# Carrier_Board.net
KiCad netlist of a schematic drawn in EAGLE
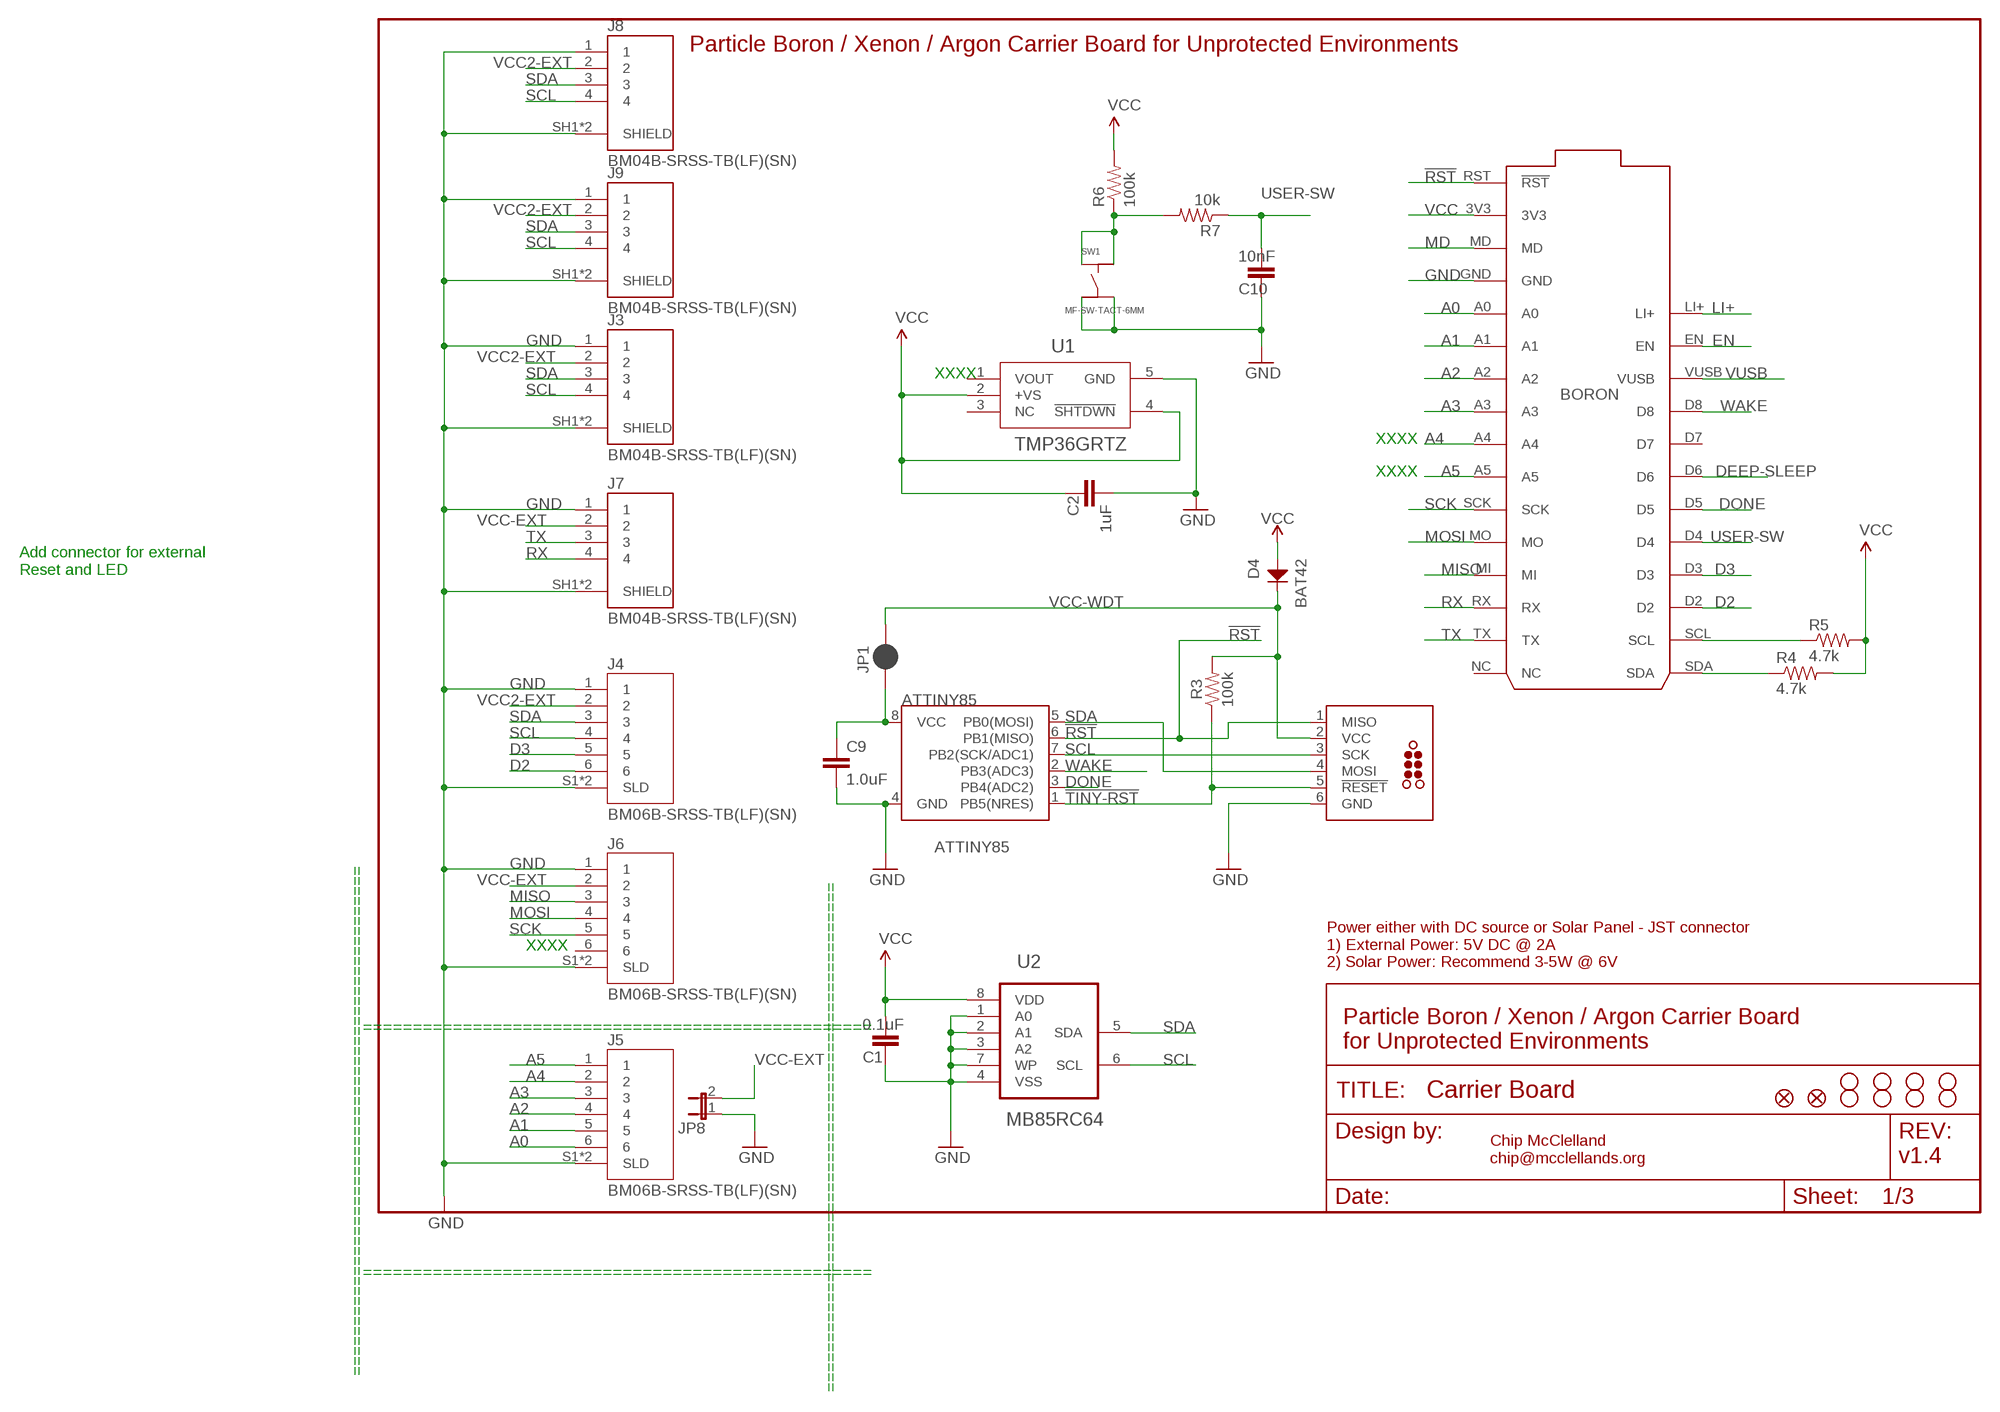
[diagram p0: schematic, sheet 1]
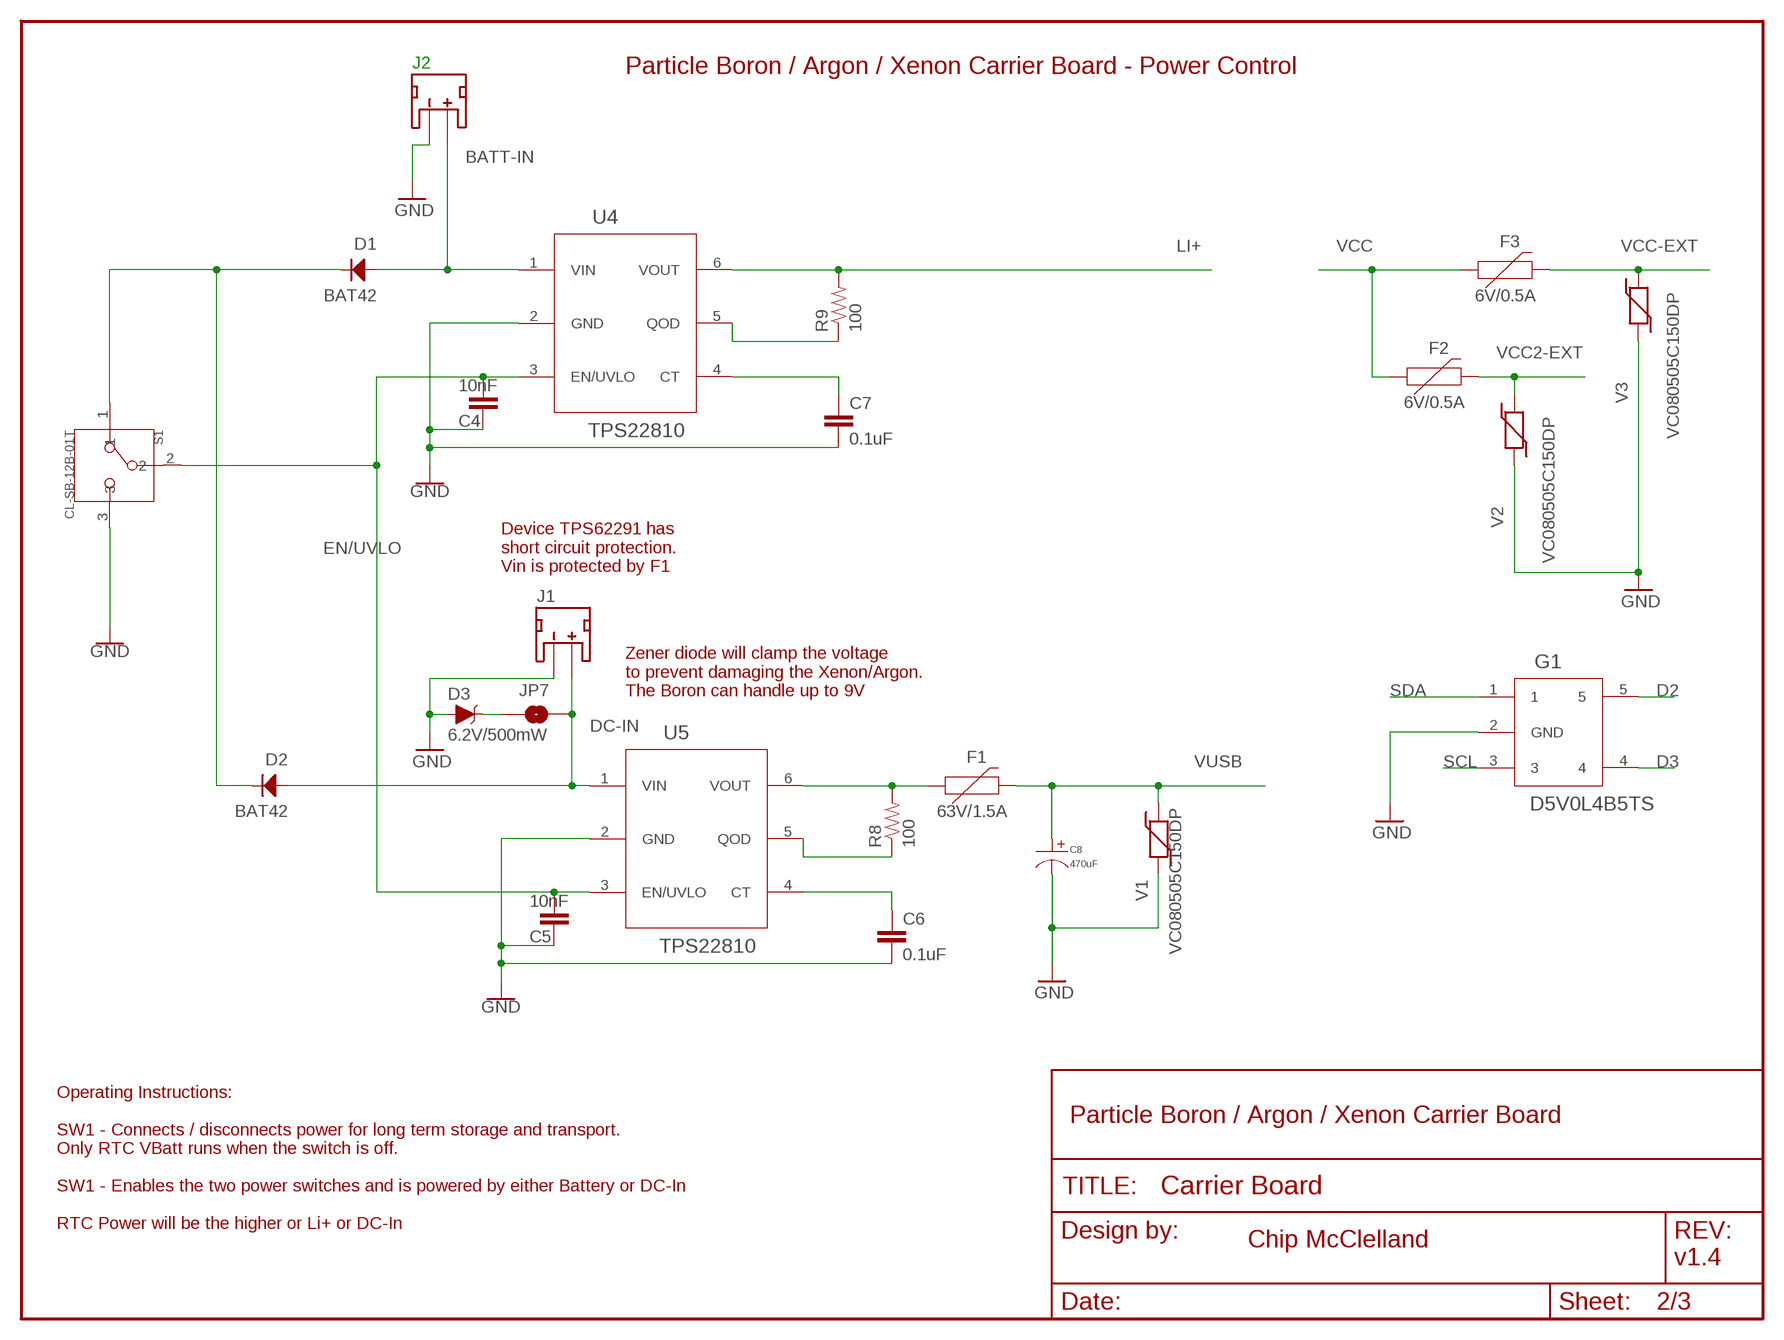
[diagram p1: schematic, sheet 2]
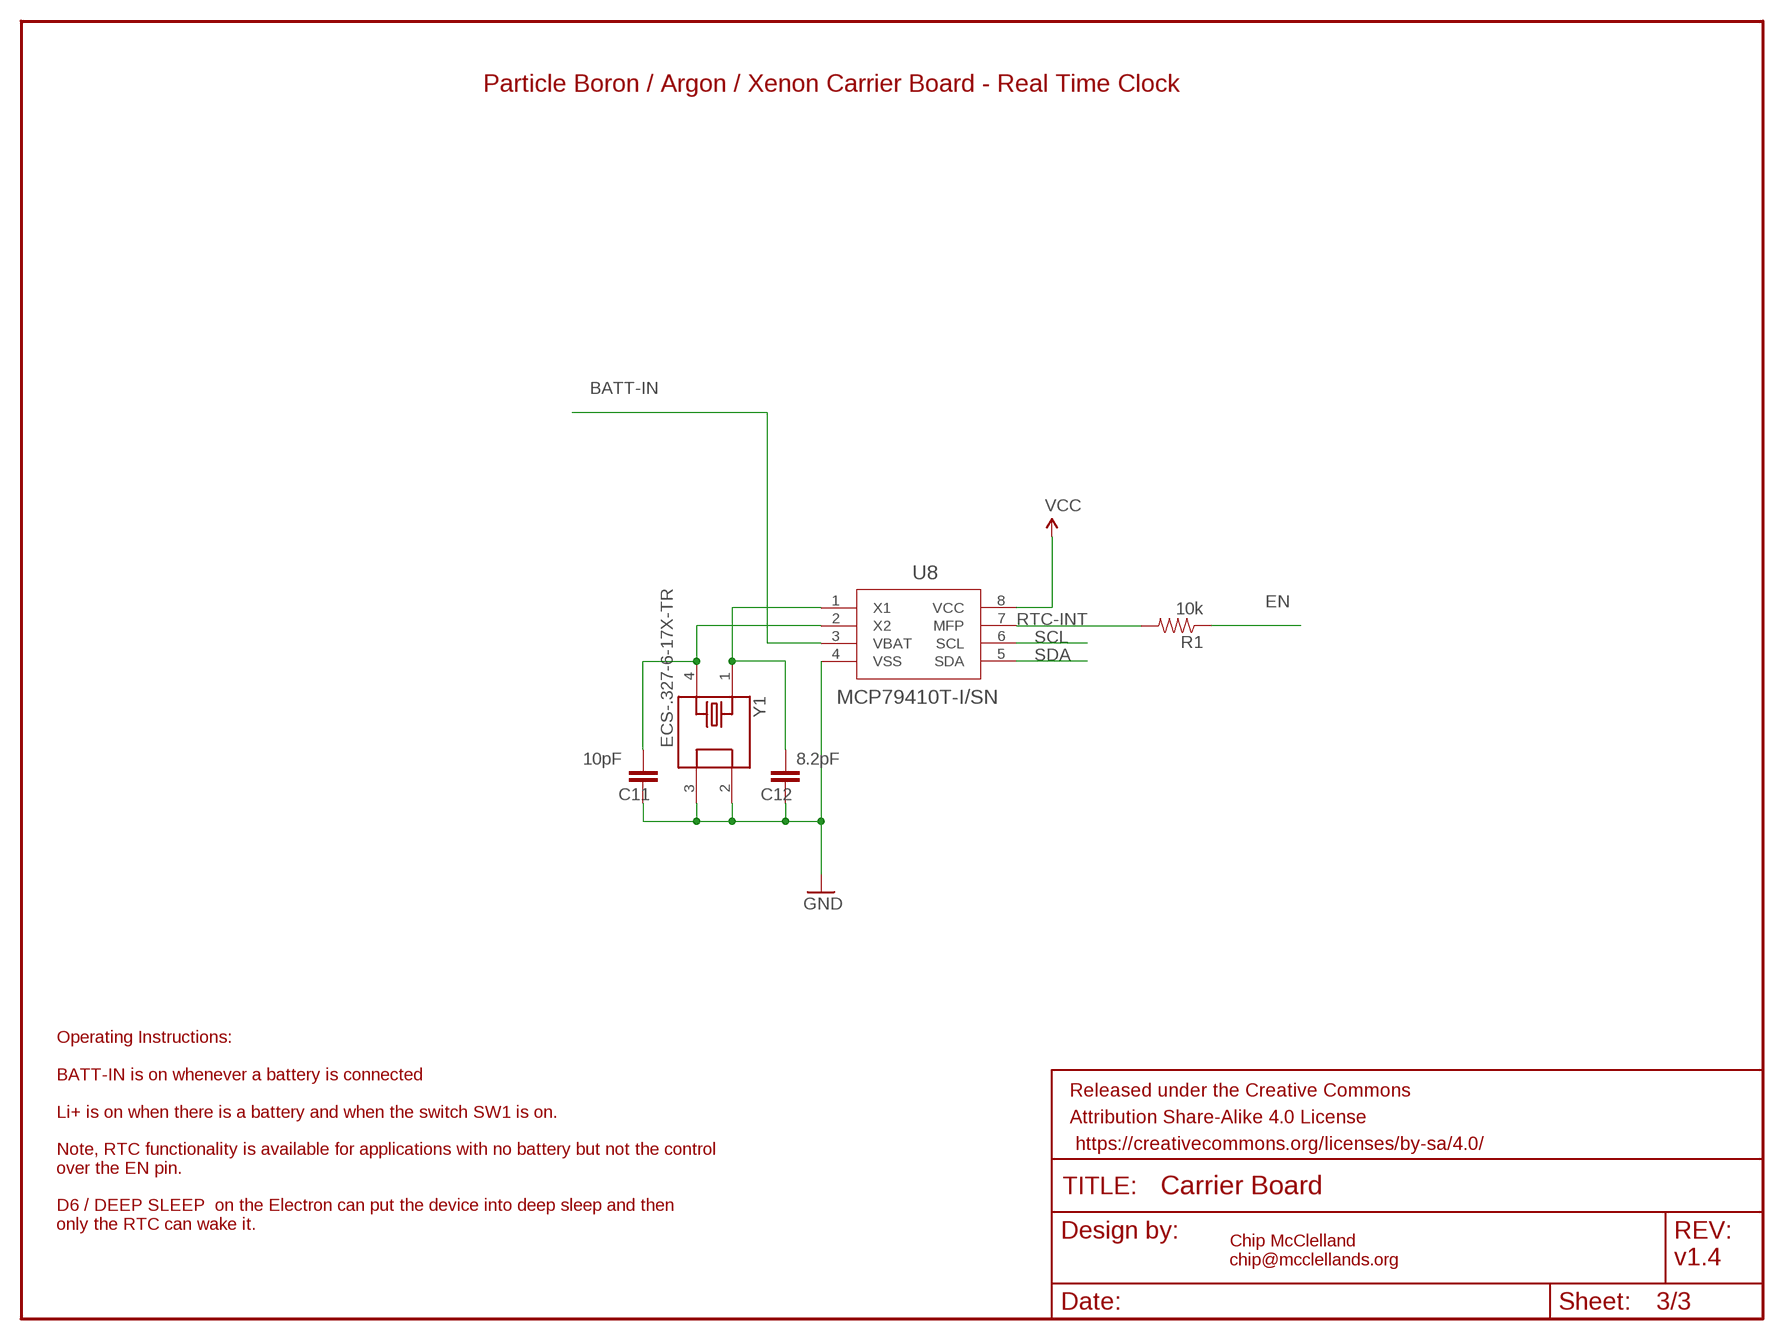
[diagram p2: schematic, sheet 3]

(export (version "E")
  (design (tool "Eeschema 10.0.6"))
  (components
    (comp (ref "C4")
      (value "10nF")
      (footprint "eagle-import:0805@1")
      (fields (field (name "HOUSEPART") "No") (field (name "MPN") "08051C103K4T2A"))
      (libsource (lib "eagle-import") (part "CAP0805"))
    )
    (comp (ref "C5")
      (value "10nF")
      (footprint "eagle-import:0805@1")
      (fields (field (name "HOUSEPART") "No") (field (name "MPN") "08051C103K4T2A"))
      (libsource (lib "eagle-import") (part "CAP0805"))
    )
    (comp (ref "C6")
      (value "0.1uF")
      (footprint "eagle-import:0805@1")
      (fields (field (name "HOUSEPART") "Yes") (field (name "MPN") "MF-CAP-0805-0.1uF"))
      (libsource (lib "eagle-import") (part "CAP0805"))
    )
    (comp (ref "C7")
      (value "0.1uF")
      (footprint "eagle-import:0805@1")
      (fields (field (name "HOUSEPART") "Yes") (field (name "MPN") "MF-CAP-0805-0.1uF"))
      (libsource (lib "eagle-import") (part "CAP0805"))
    )
    (comp (ref "C8")
      (value "470uF")
      (footprint "eagle-import:CP10MM")
      (fields (field (name "HOUSEPART") "1") (field (name "MPN") "MF-CAP-10MM-470uF"))
      (libsource (lib "eagle-import") (part "CAPACITOR_P_10MM"))
    )
    (comp (ref "D1")
      (value "BAT42")
      (footprint "eagle-import:SOD-123")
      (fields (field (name "HOUSEPART") "YES") (field (name "MPN") "MF-DIO-SOD123-BAT42"))
      (libsource (lib "eagle-import") (part "DIODES_SOD-123_BAT42"))
    )
    (comp (ref "D2")
      (value "BAT42")
      (footprint "eagle-import:SOD-123")
      (fields (field (name "HOUSEPART") "YES") (field (name "MPN") "MF-DIO-SOD123-BAT42"))
      (libsource (lib "eagle-import") (part "DIODES_SOD-123_BAT42"))
    )
    (comp (ref "D3")
      (value "6.2V/500mW")
      (footprint "eagle-import:PANASONIC_SMINI2-F5-B")
      (fields (field (name "MPN") "TDZ6V2J,115"))
      (libsource (lib "eagle-import") (part "DIODE-ZENER-DZ2J150M0L"))
    )
    (comp (ref "F1")
      (value "63V/1.5A")
      (footprint "eagle-import:1206")
      (fields (field (name "MPN") "046801.5NR"))
      (libsource (lib "eagle-import") (part "PPTC_HALF-AMP"))
    )
    (comp (ref "F2")
      (value "6V/0.5A")
      (footprint "eagle-import:1206")
      (fields (field (name "MPN") "0466.500NR"))
      (libsource (lib "eagle-import") (part "PPTC_HALF-AMP"))
    )
    (comp (ref "F3")
      (value "6V/0.5A")
      (footprint "eagle-import:1206")
      (fields (field (name "MPN") "0466.500NR"))
      (libsource (lib "eagle-import") (part "PPTC_HALF-AMP"))
    )
    (comp (ref "FRAME2")
      (value "FRAME-LETTER")
      (footprint "eagle-import:CREATIVE_COMMONS")
      (fields (field (name "POPULATE") "0"))
      (libsource (lib "eagle-import") (part "FRAME-LETTER"))
    )
    (comp (ref "G1")
      (value "D5V0L4B5TS")
      (footprint "eagle-import:SOT-23-5")
      (fields (field (name "MPN") "D5V0L4B5TS-7"))
      (libsource (lib "eagle-import") (part "D5V0L4B5TS"))
    )
    (comp (ref "J1")
      (value "S2B-PH-SM4-TB(LF)(SN)")
      (footprint "eagle-import:JST-2-SMD")
      (fields (field (name "MFG") "JST S2B-PH-SM4-TB(LF)(SN)"))
      (libsource (lib "eagle-import") (part "JST_2MM_MALE"))
    )
    (comp (ref "J2")
      (value "S2B-PH-SM4-TB(LF)(SN)")
      (footprint "eagle-import:JST-2-SMD")
      (fields (field (name "MFG") "JST S2B-PH-SM4-TB(LF)(SN)"))
      (libsource (lib "eagle-import") (part "JST_2MM_MALE"))
    )
    (comp (ref "JP7")
      (value "JUMPER-SMT_2_NO_SILK")
      (footprint "eagle-import:SMT-JUMPER_2_NO_SILK")
      (libsource (lib "eagle-import") (part "JUMPER-SMT_2_NO_SILK"))
    )
    (comp (ref "R8")
      (value "100")
      (footprint "eagle-import:0805")
      (fields (field (name "HOUSEPART") "Yes") (field (name "MPN") "MF-RES-0805-100"))
      (libsource (lib "eagle-import") (part "RESISTOR0805-RES"))
    )
    (comp (ref "R9")
      (value "100")
      (footprint "eagle-import:0805")
      (fields (field (name "HOUSEPART") "Yes") (field (name "MPN") "MF-RES-0805-100"))
      (libsource (lib "eagle-import") (part "RESISTOR0805-RES"))
    )
    (comp (ref "S1")
      (value "CL-SB-12B-01T")
      (footprint "eagle-import:CL-SB-12B")
      (fields (field (name "DIGI-KEY_PART_NUMBER") "563-1318-1-ND") (field (name "MF") "Nidec Copal"))
      (libsource (lib "eagle-import") (part "CL-SB-12B-01T"))
    )
    (comp (ref "U4")
      (value "TPS22810")
      (footprint "eagle-import:SOT-23-6")
      (fields (field (name "MPN") "TPS22810DBVT"))
      (libsource (lib "eagle-import") (part "TPS22810"))
    )
    (comp (ref "U5")
      (value "TPS22810")
      (footprint "eagle-import:SOT-23-6")
      (fields (field (name "MPN") "TPS22810DBVT"))
      (libsource (lib "eagle-import") (part "TPS22810"))
    )
    (comp (ref "V1")
      (value "VC080505C150DP")
      (footprint "eagle-import:0805")
      (libsource (lib "eagle-import") (part "VARISTOR"))
    )
    (comp (ref "V2")
      (value "VC080505C150DP")
      (footprint "eagle-import:0805")
      (libsource (lib "eagle-import") (part "VARISTOR"))
    )
    (comp (ref "V3")
      (value "VC080505C150DP")
      (footprint "eagle-import:0805")
      (libsource (lib "eagle-import") (part "VARISTOR"))
    )
    (comp (ref "ATTINY85")
      (value "ATTINY85")
      (footprint "eagle-import:SO08-EIAJ")
      (fields (field (name "MPN") "ATTINY85-20SUR"))
      (libsource (lib "eagle-import") (part "ATTINY45"))
    )
    (comp (ref "C1")
      (value "0.1uF")
      (footprint "eagle-import:0805@1")
      (fields (field (name "HOUSEPART") "YES") (field (name "MPN") "MF-CAP-0805-0.1uF"))
      (libsource (lib "eagle-import") (part "CAP0805"))
    )
    (comp (ref "C2")
      (value "1uF")
      (footprint "eagle-import:0805@1")
      (fields (field (name "MPN") "MF-CAP-0805-1uF"))
      (libsource (lib "eagle-import") (part "CAP0805"))
    )
    (comp (ref "C9")
      (value "1.0uF")
      (footprint "eagle-import:0805")
      (fields (field (name "MPN") "MF-CAP-0805-0.1uF"))
      (libsource (lib "eagle-import") (part "1.0UF-0805-25V-10%"))
    )
    (comp (ref "C10")
      (value "10nF")
      (footprint "eagle-import:0805@1")
      (fields (field (name "HOUSEPART") "No") (field (name "MPN") "08051C103K4T2A"))
      (libsource (lib "eagle-import") (part "CAP0805"))
    )
    (comp (ref "D4")
      (value "BAT42")
      (footprint "eagle-import:SOD-123")
      (fields (field (name "HOUSEPART") "YES") (field (name "MPN") "MF-DIO-SOD123-BAT42"))
      (libsource (lib "eagle-import") (part "DIODES_SOD-123_BAT42"))
    )
    (comp (ref "FD1")
      (value "FIDUCIALUFIDUCIAL")
      (footprint "eagle-import:FIDUCIAL-MICRO")
      (libsource (lib "eagle-import") (part "FIDUCIALUFIDUCIAL"))
    )
    (comp (ref "FD2")
      (value "FIDUCIALUFIDUCIAL")
      (footprint "eagle-import:FIDUCIAL-MICRO")
      (libsource (lib "eagle-import") (part "FIDUCIALUFIDUCIAL"))
    )
    (comp (ref "FRAME1")
      (value "FRAME-LETTER")
      (footprint "eagle-import:CREATIVE_COMMONS")
      (fields (field (name "POPULATE") "0"))
      (libsource (lib "eagle-import") (part "FRAME-LETTER"))
    )
    (comp (ref "H1")
      (value "STAND-OFF-M2.5")
      (footprint "eagle-import:STAND-OFF-M2.5")
      (libsource (lib "eagle-import") (part "STAND-OFF-M2.5"))
    )
    (comp (ref "H2")
      (value "STAND-OFF-M2.5")
      (footprint "eagle-import:STAND-OFF-M2.5")
      (libsource (lib "eagle-import") (part "STAND-OFF-M2.5"))
    )
    (comp (ref "H3")
      (value "STAND-OFF-M2.5")
      (footprint "eagle-import:STAND-OFF-M2.5")
      (libsource (lib "eagle-import") (part "STAND-OFF-M2.5"))
    )
    (comp (ref "H4")
      (value "STAND-OFF-M2.5")
      (footprint "eagle-import:STAND-OFF-M2.5")
      (libsource (lib "eagle-import") (part "STAND-OFF-M2.5"))
    )
    (comp (ref "ICSP")
      (value "TCP2030-MCP-NL")
      (footprint "eagle-import:TC2030-MCP-NL")
      (libsource (lib "eagle-import") (part "TCP2030-MCP-NL"))
    )
    (comp (ref "J3")
      (value "BM04B-SRSS-TB(LF)(SN)")
      (footprint "eagle-import:CONN_BM04B-SRSS-TBT(LF)(SN)")
      (fields (field (name "MF") "JST Sales") (field (name "MP") "BM04B-SRSS-TB_LF__SN_"))
      (libsource (lib "eagle-import") (part "BM04B-SRSS-TBT(LF)(SN)"))
    )
    (comp (ref "J4")
      (value "BM06B-SRSS-TB(LF)(SN)")
      (footprint "eagle-import:JST_BM06B-SRSS-TB(LF)(SN)")
      (libsource (lib "eagle-import") (part "BM06B-SRSS-TB(LF)(SN)"))
    )
    (comp (ref "J5")
      (value "BM06B-SRSS-TB(LF)(SN)")
      (footprint "eagle-import:JST_BM06B-SRSS-TB(LF)(SN)")
      (libsource (lib "eagle-import") (part "BM06B-SRSS-TB(LF)(SN)"))
    )
    (comp (ref "J6")
      (value "BM06B-SRSS-TB(LF)(SN)")
      (footprint "eagle-import:JST_BM06B-SRSS-TB(LF)(SN)")
      (libsource (lib "eagle-import") (part "BM06B-SRSS-TB(LF)(SN)"))
    )
    (comp (ref "J7")
      (value "BM04B-SRSS-TB(LF)(SN)")
      (footprint "eagle-import:CONN_BM04B-SRSS-TBT(LF)(SN)")
      (fields (field (name "MF") "JST Sales") (field (name "MP") "BM04B-SRSS-TB_LF__SN_"))
      (libsource (lib "eagle-import") (part "BM04B-SRSS-TBT(LF)(SN)"))
    )
    (comp (ref "J8")
      (value "BM04B-SRSS-TB(LF)(SN)")
      (footprint "eagle-import:CONN_BM04B-SRSS-TBT(LF)(SN)")
      (fields (field (name "MF") "JST Sales") (field (name "MP") "BM04B-SRSS-TB_LF__SN_"))
      (libsource (lib "eagle-import") (part "BM04B-SRSS-TBT(LF)(SN)"))
    )
    (comp (ref "J9")
      (value "BM04B-SRSS-TB(LF)(SN)")
      (footprint "eagle-import:CONN_BM04B-SRSS-TBT(LF)(SN)")
      (fields (field (name "MF") "JST Sales") (field (name "MP") "BM04B-SRSS-TB_LF__SN_"))
      (libsource (lib "eagle-import") (part "BM04B-SRSS-TBT(LF)(SN)"))
    )
    (comp (ref "JP1")
      (value "JUMPER-SMT_2_NC_PASTE_SILK")
      (footprint "eagle-import:SMT-JUMPER_2_NC_PASTE_SILK")
      (libsource (lib "eagle-import") (part "JUMPER-SMT_2_NC_PASTE_SILK"))
    )
    (comp (ref "JP3")
      (value "STAND-OFF")
      (footprint "eagle-import:STAND-OFF")
      (libsource (lib "eagle-import") (part "STAND-OFF"))
    )
    (comp (ref "JP4")
      (value "STAND-OFF")
      (footprint "eagle-import:STAND-OFF")
      (libsource (lib "eagle-import") (part "STAND-OFF"))
    )
    (comp (ref "JP5")
      (value "STAND-OFF")
      (footprint "eagle-import:STAND-OFF")
      (libsource (lib "eagle-import") (part "STAND-OFF"))
    )
    (comp (ref "JP6")
      (value "STAND-OFF")
      (footprint "eagle-import:STAND-OFF")
      (libsource (lib "eagle-import") (part "STAND-OFF"))
    )
    (comp (ref "JP8")
      (value "JP1E")
      (footprint "eagle-import:JP1")
      (libsource (lib "eagle-import") (part "JP1E"))
    )
    (comp (ref "P1")
      (value "Particle Boron / Xenon / Argon")
      (footprint "eagle-import:PARTICLE-DEVICES_BORON")
      (libsource (lib "eagle-import") (part "PARTICLE-DEVICES-BORON"))
    )
    (comp (ref "R3")
      (value "100k")
      (footprint "eagle-import:0805")
      (fields (field (name "MPN") "MF-RES-0805-100K"))
      (libsource (lib "eagle-import") (part "0.3OHM-0805-1/8W-1%"))
    )
    (comp (ref "R4")
      (value "4.7k")
      (footprint "eagle-import:0805")
      (fields (field (name "MPN") "MF-RES-0805-4.7K"))
      (libsource (lib "eagle-import") (part "RESISTOR0805-RES"))
    )
    (comp (ref "R5")
      (value "4.7k")
      (footprint "eagle-import:0805")
      (fields (field (name "MPN") "MF-RES-0805-4.7K"))
      (libsource (lib "eagle-import") (part "RESISTOR0805-RES"))
    )
    (comp (ref "R6")
      (value "100k")
      (footprint "eagle-import:0805")
      (fields (field (name "HOUSEPART") "YES") (field (name "MPN") "MF-RES-0805-100K"))
      (libsource (lib "eagle-import") (part "RESISTOR0805-RES"))
    )
    (comp (ref "R7")
      (value "10k")
      (footprint "eagle-import:0805")
      (fields (field (name "HOUSEPART") "YES") (field (name "MPN") "MF-RES-0805-10K"))
      (libsource (lib "eagle-import") (part "RESISTOR0805-RES"))
    )
    (comp (ref "SW1")
      (value "MF-SW-TACT-6MM")
      (footprint "eagle-import:TACT6MM")
      (fields (field (name "HOUSEPART") "YES"))
      (libsource (lib "eagle-import") (part "TACT_6MM"))
    )
    (comp (ref "U1")
      (value "TMP36GRTZ")
      (footprint "eagle-import:RJ_5")
      (fields
        (field (name "MANUFACTURER_PART_NUMBER") "TMP36GRTZREEL7")
        (field (name "MANUFACTURER_PART_NUMBER_1") "TMP36GRTZ-REEL7")
        (field (name "MPN") "TMP36GRTZ-REEL7")
      )
      (libsource (lib "eagle-import") (part "TMP36GRTZ-REEL7"))
    )
    (comp (ref "U2")
      (value "MB85RC64")
      (footprint "eagle-import:SOIC127P600X175-8N")
      (fields (field (name "MPN") "MB85RC128PNF-G-JNE1") (field (name "MPN_1") "MB85RC64APNF-G-JNERE1"))
      (libsource (lib "eagle-import") (part "MB85RC128PNF-G-JNE1"))
    )
    (comp (ref "C11")
      (value "10pF")
      (footprint "eagle-import:0805@1")
      (fields (field (name "HOUSEPART") "No") (field (name "MPN") "C0805C100JDGACTU‎"))
      (libsource (lib "eagle-import") (part "CAP0805"))
    )
    (comp (ref "C12")
      (value "8.2pF")
      (footprint "eagle-import:0805@1")
      (fields (field (name "HOUSEPART") "No") (field (name "MPN") "C0805C829D5GACTU‎"))
      (libsource (lib "eagle-import") (part "CAP0805"))
    )
    (comp (ref "FRAME3")
      (value "FRAME-LETTER")
      (footprint "eagle-import:CREATIVE_COMMONS")
      (fields (field (name "POPULATE") "0"))
      (libsource (lib "eagle-import") (part "SparkFun-Aesthetics_507_FRAME-LETTER"))
    )
    (comp (ref "R1")
      (value "10k")
      (footprint "eagle-import:0805")
      (fields (field (name "HOUSEPART") "YES") (field (name "MPN") "MF-RES-0805-10K"))
      (libsource (lib "eagle-import") (part "RESISTOR0805-RES"))
    )
    (comp (ref "U8")
      (value "MCP79410T-I/SN")
      (footprint "eagle-import:SOIC8-N_MC")
      (fields (field (name "MANUFACTURER_PART_NUMBER") "MCP79410TISN"))
      (libsource (lib "eagle-import") (part "MCP79410T-I/SN"))
    )
    (comp (ref "Y1")
      (value "ECS-.327-6-17X-TR")
      (footprint "eagle-import:XTAL_ECS-.327-6-17X-TR")
      (fields (field (name "DIGI-KEY_PART_NUMBER") "XC1307CT-ND") (field (name "MF") "ECS Inc."))
      (libsource (lib "eagle-import") (part "ECS-.327-6-17X-TR"))
    )
  )
  (nets
    (net (code "1") (name "A0") (class "Default")
      (node (ref "J5") (pin "6") (pinfunction "6_6") (pintype "passive"))
      (node (ref "P1") (pin "A0") (pinfunction "A0_A0") (pintype "bidirectional"))
    )
    (net (code "2") (name "A1") (class "Default")
      (node (ref "J5") (pin "5") (pinfunction "5_5") (pintype "passive"))
      (node (ref "P1") (pin "A1") (pinfunction "A1_A1") (pintype "bidirectional"))
    )
    (net (code "3") (name "A2") (class "Default")
      (node (ref "J5") (pin "4") (pinfunction "4_4") (pintype "passive"))
      (node (ref "P1") (pin "A2") (pinfunction "A2_A2") (pintype "bidirectional"))
    )
    (net (code "4") (name "A3") (class "Default")
      (node (ref "J5") (pin "3") (pinfunction "3_3") (pintype "passive"))
      (node (ref "P1") (pin "A3") (pinfunction "A3_A3") (pintype "bidirectional"))
    )
    (net (code "5") (name "A4") (class "Default")
      (node (ref "J5") (pin "2") (pinfunction "2_2") (pintype "passive"))
      (node (ref "P1") (pin "A4") (pinfunction "A4_A4") (pintype "bidirectional"))
    )
    (net (code "6") (name "A5") (class "Default")
      (node (ref "J5") (pin "1") (pinfunction "1_1") (pintype "passive"))
      (node (ref "P1") (pin "A5") (pinfunction "A5_A5") (pintype "bidirectional"))
    )
    (net (code "7") (name "BATT-IN") (class "Default")
      (node (ref "D1") (pin "ANODE") (pinfunction "ANODE_ANODE") (pintype "bidirectional"))
      (node (ref "J2") (pin "2") (pinfunction "+_2") (pintype "bidirectional"))
      (node (ref "U4") (pin "1") (pinfunction "VIN_1") (pintype "power_in"))
      (node (ref "U8") (pin "3") (pinfunction "VBAT_3") (pintype "input"))
    )
    (net (code "8") (name "D2") (class "Default")
      (node (ref "G1") (pin "5") (pinfunction "5_5") (pintype "output"))
      (node (ref "J4") (pin "6") (pinfunction "6_6") (pintype "passive"))
      (node (ref "P1") (pin "D2") (pinfunction "D2_D2") (pintype "bidirectional"))
    )
    (net (code "9") (name "D3") (class "Default")
      (node (ref "G1") (pin "4") (pinfunction "4_4") (pintype "output"))
      (node (ref "J4") (pin "5") (pinfunction "5_5") (pintype "passive"))
      (node (ref "P1") (pin "D3") (pinfunction "D3_D3") (pintype "bidirectional"))
    )
    (net (code "10") (name "DC-IN") (class "Default")
      (node (ref "D2") (pin "ANODE") (pinfunction "ANODE_ANODE") (pintype "bidirectional"))
      (node (ref "J1") (pin "2") (pinfunction "+_2") (pintype "bidirectional"))
      (node (ref "JP7") (pin "1") (pinfunction "1_1") (pintype "passive"))
      (node (ref "U5") (pin "1") (pinfunction "VIN_1") (pintype "power_in"))
    )
    (net (code "11") (name "DEEP-SLEEP") (class "Default")
      (node (ref "P1") (pin "D6") (pinfunction "D6_D6") (pintype "bidirectional"))
    )
    (net (code "12") (name "DONE") (class "Default")
      (node (ref "ATTINY85") (pin "3") (pinfunction "PB4(ADC2)_3") (pintype "bidirectional"))
      (node (ref "P1") (pin "D5") (pinfunction "D5_D5") (pintype "bidirectional"))
    )
    (net (code "13") (name "EN") (class "Default")
      (node (ref "P1") (pin "EN") (pinfunction "EN_EN") (pintype "bidirectional"))
      (node (ref "R1") (pin "1") (pinfunction "1_1") (pintype "passive"))
    )
    (net (code "14") (name "EN{slash}UVLO") (class "Default")
      (node (ref "C4") (pin "1") (pinfunction "1_1") (pintype "passive"))
      (node (ref "C5") (pin "1") (pinfunction "1_1") (pintype "passive"))
      (node (ref "S1") (pin "2") (pinfunction "2_2") (pintype "bidirectional"))
      (node (ref "U4") (pin "3") (pinfunction "EN/UVLO_3") (pintype "input"))
      (node (ref "U5") (pin "3") (pinfunction "EN/UVLO_3") (pintype "input"))
    )
    (net (code "15") (name "GND") (class "Default")
      (node (ref "ATTINY85") (pin "4") (pinfunction "GND_4") (pintype "bidirectional"))
      (node (ref "C1") (pin "2") (pinfunction "2_2") (pintype "passive"))
      (node (ref "C10") (pin "2") (pinfunction "2_2") (pintype "passive"))
      (node (ref "C11") (pin "2") (pinfunction "2_2") (pintype "passive"))
      (node (ref "C12") (pin "2") (pinfunction "2_2") (pintype "passive"))
      (node (ref "C2") (pin "2") (pinfunction "2_2") (pintype "passive"))
      (node (ref "C4") (pin "2") (pinfunction "2_2") (pintype "passive"))
      (node (ref "C5") (pin "2") (pinfunction "2_2") (pintype "passive"))
      (node (ref "C6") (pin "2") (pinfunction "2_2") (pintype "passive"))
      (node (ref "C7") (pin "2") (pinfunction "2_2") (pintype "passive"))
      (node (ref "C8") (pin "P$2") (pinfunction "P$2_P$2") (pintype "passive"))
      (node (ref "C9") (pin "2") (pinfunction "2_2") (pintype "passive"))
      (node (ref "D3") (pin "A") (pinfunction "A_A") (pintype "passive"))
      (node (ref "G1") (pin "2") (pinfunction "GND_2") (pintype "power_in"))
      (node (ref "ICSP") (pin "6") (pinfunction "GND_6") (pintype "power_in"))
      (node (ref "J1") (pin "1") (pinfunction "-_1") (pintype "bidirectional"))
      (node (ref "J2") (pin "1") (pinfunction "-_1") (pintype "bidirectional"))
      (node (ref "J3") (pin "1") (pinfunction "1_1") (pintype "passive"))
      (node (ref "J3") (pin "SH1") (pinfunction "SHIELD_SH1") (pintype "passive"))
      (node (ref "J3") (pin "SH2") (pinfunction "SHIELD_SH2") (pintype "passive"))
      (node (ref "J4") (pin "1") (pinfunction "1_1") (pintype "passive"))
      (node (ref "J4") (pin "S1") (pinfunction "SLD_S1") (pintype "passive"))
      (node (ref "J4") (pin "S2") (pinfunction "SLD_S2") (pintype "passive"))
      (node (ref "J5") (pin "S1") (pinfunction "SLD_S1") (pintype "passive"))
      (node (ref "J5") (pin "S2") (pinfunction "SLD_S2") (pintype "passive"))
      (node (ref "J6") (pin "1") (pinfunction "1_1") (pintype "passive"))
      (node (ref "J6") (pin "S1") (pinfunction "SLD_S1") (pintype "passive"))
      (node (ref "J6") (pin "S2") (pinfunction "SLD_S2") (pintype "passive"))
      (node (ref "J7") (pin "1") (pinfunction "1_1") (pintype "passive"))
      (node (ref "J7") (pin "SH1") (pinfunction "SHIELD_SH1") (pintype "passive"))
      (node (ref "J7") (pin "SH2") (pinfunction "SHIELD_SH2") (pintype "passive"))
      (node (ref "J8") (pin "1") (pinfunction "1_1") (pintype "passive"))
      (node (ref "J8") (pin "SH1") (pinfunction "SHIELD_SH1") (pintype "passive"))
      (node (ref "J8") (pin "SH2") (pinfunction "SHIELD_SH2") (pintype "passive"))
      (node (ref "J9") (pin "1") (pinfunction "1_1") (pintype "passive"))
      (node (ref "J9") (pin "SH1") (pinfunction "SHIELD_SH1") (pintype "passive"))
      (node (ref "J9") (pin "SH2") (pinfunction "SHIELD_SH2") (pintype "passive"))
      (node (ref "JP8") (pin "1") (pinfunction "1_1") (pintype "passive"))
      (node (ref "P1") (pin "GND") (pinfunction "GND_GND") (pintype "bidirectional"))
      (node (ref "S1") (pin "3") (pinfunction "3_3") (pintype "bidirectional"))
      (node (ref "SW1") (pin "P$3") (pinfunction "P$3_P$3") (pintype "bidirectional"))
      (node (ref "SW1") (pin "P$4") (pinfunction "P$4_P$4") (pintype "bidirectional"))
      (node (ref "U1") (pin "5") (pinfunction "GND_5") (pintype "passive"))
      (node (ref "U2") (pin "1") (pinfunction "A0_1") (pintype "input"))
      (node (ref "U2") (pin "2") (pinfunction "A1_2") (pintype "input"))
      (node (ref "U2") (pin "3") (pinfunction "A2_3") (pintype "input"))
      (node (ref "U2") (pin "4") (pinfunction "VSS_4") (pintype "passive"))
      (node (ref "U2") (pin "7") (pinfunction "WP_7") (pintype "input"))
      (node (ref "U4") (pin "2") (pinfunction "GND_2") (pintype "power_in"))
      (node (ref "U5") (pin "2") (pinfunction "GND_2") (pintype "power_in"))
      (node (ref "U8") (pin "4") (pinfunction "VSS_4") (pintype "power_in"))
      (node (ref "V1") (pin "1") (pinfunction "1_1") (pintype "passive"))
      (node (ref "V2") (pin "1") (pinfunction "1_1") (pintype "passive"))
      (node (ref "V3") (pin "1") (pinfunction "1_1") (pintype "passive"))
      (node (ref "Y1") (pin "2") (pinfunction "2_2") (pintype "passive"))
      (node (ref "Y1") (pin "3") (pinfunction "3_3") (pintype "passive"))
    )
    (net (code "16") (name "LI+") (class "Default")
      (node (ref "P1") (pin "LI+") (pinfunction "LI+_LI+") (pintype "bidirectional"))
      (node (ref "R9") (pin "2") (pinfunction "2_2") (pintype "passive"))
      (node (ref "U4") (pin "6") (pinfunction "VOUT_6") (pintype "power_in"))
    )
    (net (code "17") (name "MD") (class "Default")
      (node (ref "P1") (pin "MD") (pinfunction "MD_MD") (pintype "bidirectional"))
    )
    (net (code "18") (name "MISO") (class "Default")
      (node (ref "J6") (pin "3") (pinfunction "3_3") (pintype "passive"))
      (node (ref "P1") (pin "MI") (pinfunction "MI_MI") (pintype "bidirectional"))
    )
    (net (code "19") (name "MOSI") (class "Default")
      (node (ref "J6") (pin "4") (pinfunction "4_4") (pintype "passive"))
      (node (ref "P1") (pin "MO") (pinfunction "MO_MO") (pintype "bidirectional"))
    )
    (net (code "20") (name "Net-(ATTINY85-VCC)") (class "Default")
      (node (ref "ATTINY85") (pin "8") (pinfunction "VCC_8") (pintype "bidirectional"))
      (node (ref "C9") (pin "1") (pinfunction "1_1") (pintype "passive"))
      (node (ref "JP1") (pin "1") (pinfunction "1_1") (pintype "passive"))
    )
    (net (code "21") (name "Net-(D1-PadCATHODE)") (class "Default")
      (node (ref "D1") (pin "CATHODE") (pinfunction "CATHODE_CATHODE") (pintype "bidirectional"))
      (node (ref "D2") (pin "CATHODE") (pinfunction "CATHODE_CATHODE") (pintype "bidirectional"))
      (node (ref "S1") (pin "1") (pinfunction "1_1") (pintype "bidirectional"))
    )
    (net (code "22") (name "Net-(D3-PadC)") (class "Default")
      (node (ref "D3") (pin "C") (pinfunction "C_C") (pintype "passive"))
      (node (ref "JP7") (pin "2") (pinfunction "2_2") (pintype "passive"))
    )
    (net (code "23") (name "Net-(R6-Pad1)") (class "Default")
      (node (ref "R6") (pin "1") (pinfunction "1_1") (pintype "passive"))
      (node (ref "R7") (pin "2") (pinfunction "2_2") (pintype "passive"))
      (node (ref "SW1") (pin "P$1") (pinfunction "P$1_P$1") (pintype "bidirectional"))
      (node (ref "SW1") (pin "P$2") (pinfunction "P$2_P$2") (pintype "bidirectional"))
    )
    (net (code "24") (name "Net-(U4-CT)") (class "Default")
      (node (ref "C7") (pin "1") (pinfunction "1_1") (pintype "passive"))
      (node (ref "U4") (pin "4") (pinfunction "CT_4") (pintype "bidirectional"))
    )
    (net (code "25") (name "Net-(U4-QOD)") (class "Default")
      (node (ref "R9") (pin "1") (pinfunction "1_1") (pintype "passive"))
      (node (ref "U4") (pin "5") (pinfunction "QOD_5") (pintype "bidirectional"))
    )
    (net (code "26") (name "Net-(U5-CT)") (class "Default")
      (node (ref "C6") (pin "1") (pinfunction "1_1") (pintype "passive"))
      (node (ref "U5") (pin "4") (pinfunction "CT_4") (pintype "bidirectional"))
    )
    (net (code "27") (name "Net-(U5-QOD)") (class "Default")
      (node (ref "R8") (pin "1") (pinfunction "1_1") (pintype "passive"))
      (node (ref "U5") (pin "5") (pinfunction "QOD_5") (pintype "bidirectional"))
    )
    (net (code "28") (name "Net-(U5-VOUT)") (class "Default")
      (node (ref "F1") (pin "1") (pinfunction "1_1") (pintype "bidirectional"))
      (node (ref "R8") (pin "2") (pinfunction "2_2") (pintype "passive"))
      (node (ref "U5") (pin "6") (pinfunction "VOUT_6") (pintype "power_in"))
    )
    (net (code "29") (name "Net-(U8-X1)") (class "Default")
      (node (ref "C12") (pin "1") (pinfunction "1_1") (pintype "passive"))
      (node (ref "U8") (pin "1") (pinfunction "X1_1") (pintype "input"))
      (node (ref "Y1") (pin "1") (pinfunction "1_1") (pintype "passive"))
    )
    (net (code "30") (name "Net-(U8-X2)") (class "Default")
      (node (ref "C11") (pin "1") (pinfunction "1_1") (pintype "passive"))
      (node (ref "U8") (pin "2") (pinfunction "X2_2") (pintype "output"))
      (node (ref "Y1") (pin "4") (pinfunction "4_4") (pintype "passive"))
    )
    (net (code "31") (name "RTC-INT") (class "Default")
      (node (ref "R1") (pin "2") (pinfunction "2_2") (pintype "passive"))
      (node (ref "U8") (pin "7") (pinfunction "MFP_7") (pintype "passive"))
    )
    (net (code "32") (name "RX") (class "Default")
      (node (ref "J7") (pin "4") (pinfunction "4_4") (pintype "passive"))
      (node (ref "P1") (pin "RX") (pinfunction "RX_RX") (pintype "bidirectional"))
    )
    (net (code "33") (name "SCK") (class "Default")
      (node (ref "J6") (pin "5") (pinfunction "5_5") (pintype "passive"))
      (node (ref "P1") (pin "SCK") (pinfunction "SCK_SCK") (pintype "bidirectional"))
    )
    (net (code "34") (name "SCL") (class "Default")
      (node (ref "ATTINY85") (pin "7") (pinfunction "PB2(SCK/ADC1)_7") (pintype "bidirectional"))
      (node (ref "G1") (pin "3") (pinfunction "3_3") (pintype "input"))
      (node (ref "ICSP") (pin "3") (pinfunction "SCK_3") (pintype "bidirectional"))
      (node (ref "J3") (pin "4") (pinfunction "4_4") (pintype "passive"))
      (node (ref "J4") (pin "4") (pinfunction "4_4") (pintype "passive"))
      (node (ref "J8") (pin "4") (pinfunction "4_4") (pintype "passive"))
      (node (ref "J9") (pin "4") (pinfunction "4_4") (pintype "passive"))
      (node (ref "P1") (pin "SCL") (pinfunction "SCL_SCL") (pintype "bidirectional"))
      (node (ref "R5") (pin "1") (pinfunction "1_1") (pintype "passive"))
      (node (ref "U2") (pin "6") (pinfunction "SCL_6") (pintype "input"))
      (node (ref "U8") (pin "6") (pinfunction "SCL_6") (pintype "input"))
    )
    (net (code "35") (name "SDA") (class "Default")
      (node (ref "ATTINY85") (pin "5") (pinfunction "PB0(MOSI)_5") (pintype "bidirectional"))
      (node (ref "G1") (pin "1") (pinfunction "1_1") (pintype "input"))
      (node (ref "ICSP") (pin "4") (pinfunction "MOSI_4") (pintype "bidirectional"))
      (node (ref "J3") (pin "3") (pinfunction "3_3") (pintype "passive"))
      (node (ref "J4") (pin "3") (pinfunction "3_3") (pintype "passive"))
      (node (ref "J8") (pin "3") (pinfunction "3_3") (pintype "passive"))
      (node (ref "J9") (pin "3") (pinfunction "3_3") (pintype "passive"))
      (node (ref "P1") (pin "SDA") (pinfunction "SDA_SDA") (pintype "bidirectional"))
      (node (ref "R4") (pin "1") (pinfunction "1_1") (pintype "passive"))
      (node (ref "U2") (pin "5") (pinfunction "SDA_5") (pintype "bidirectional"))
      (node (ref "U8") (pin "5") (pinfunction "SDA_5") (pintype "bidirectional"))
    )
    (net (code "36") (name "TX") (class "Default")
      (node (ref "J7") (pin "3") (pinfunction "3_3") (pintype "passive"))
      (node (ref "P1") (pin "TX") (pinfunction "TX_TX") (pintype "bidirectional"))
    )
    (net (code "37") (name "USER-SW") (class "Default")
      (node (ref "C10") (pin "1") (pinfunction "1_1") (pintype "passive"))
      (node (ref "P1") (pin "D4") (pinfunction "D4_D4") (pintype "bidirectional"))
      (node (ref "R7") (pin "1") (pinfunction "1_1") (pintype "passive"))
    )
    (net (code "38") (name "VCC") (class "Default")
      (node (ref "C1") (pin "1") (pinfunction "1_1") (pintype "passive"))
      (node (ref "C2") (pin "1") (pinfunction "1_1") (pintype "passive"))
      (node (ref "D4") (pin "ANODE") (pinfunction "ANODE_ANODE") (pintype "bidirectional"))
      (node (ref "F2") (pin "1") (pinfunction "1_1") (pintype "bidirectional"))
      (node (ref "F3") (pin "1") (pinfunction "1_1") (pintype "bidirectional"))
      (node (ref "P1") (pin "3V3") (pinfunction "3V3_3V3") (pintype "bidirectional"))
      (node (ref "R4") (pin "2") (pinfunction "2_2") (pintype "passive"))
      (node (ref "R5") (pin "2") (pinfunction "2_2") (pintype "passive"))
      (node (ref "R6") (pin "2") (pinfunction "2_2") (pintype "passive"))
      (node (ref "U1") (pin "2") (pinfunction "+VS_2") (pintype "power_in"))
      (node (ref "U1") (pin "4") (pinfunction "~{SHTDWN}_4") (pintype "passive"))
      (node (ref "U2") (pin "8") (pinfunction "VDD_8") (pintype "power_in"))
      (node (ref "U8") (pin "8") (pinfunction "VCC_8") (pintype "power_in"))
    )
    (net (code "39") (name "VCC-EXT") (class "Default")
      (node (ref "F3") (pin "2") (pinfunction "2_2") (pintype "bidirectional"))
      (node (ref "J6") (pin "2") (pinfunction "2_2") (pintype "passive"))
      (node (ref "J7") (pin "2") (pinfunction "2_2") (pintype "passive"))
      (node (ref "JP8") (pin "2") (pinfunction "2_2") (pintype "passive"))
      (node (ref "V3") (pin "2") (pinfunction "2_2") (pintype "passive"))
    )
    (net (code "40") (name "VCC-WDT") (class "Default")
      (node (ref "D4") (pin "CATHODE") (pinfunction "CATHODE_CATHODE") (pintype "bidirectional"))
      (node (ref "ICSP") (pin "2") (pinfunction "VCC_2") (pintype "power_in"))
      (node (ref "JP1") (pin "2") (pinfunction "2_2") (pintype "passive"))
      (node (ref "R3") (pin "2") (pinfunction "2_2") (pintype "passive"))
    )
    (net (code "41") (name "VCC2-EXT") (class "Default")
      (node (ref "F2") (pin "2") (pinfunction "2_2") (pintype "bidirectional"))
      (node (ref "J3") (pin "2") (pinfunction "2_2") (pintype "passive"))
      (node (ref "J4") (pin "2") (pinfunction "2_2") (pintype "passive"))
      (node (ref "J8") (pin "2") (pinfunction "2_2") (pintype "passive"))
      (node (ref "J9") (pin "2") (pinfunction "2_2") (pintype "passive"))
      (node (ref "V2") (pin "2") (pinfunction "2_2") (pintype "passive"))
    )
    (net (code "42") (name "VUSB") (class "Default")
      (node (ref "C8") (pin "P$1") (pinfunction "P$1_P$1") (pintype "passive"))
      (node (ref "F1") (pin "2") (pinfunction "2_2") (pintype "bidirectional"))
      (node (ref "P1") (pin "VUSB") (pinfunction "VUSB_VUSB") (pintype "bidirectional"))
      (node (ref "V1") (pin "2") (pinfunction "2_2") (pintype "passive"))
    )
    (net (code "43") (name "WAKE") (class "Default")
      (node (ref "ATTINY85") (pin "2") (pinfunction "PB3(ADC3)_2") (pintype "bidirectional"))
      (node (ref "P1") (pin "D8") (pinfunction "D8_D8") (pintype "bidirectional"))
    )
    (net (code "44") (name "unconnected-(J1-PAD1-PadNC1)") (class "Default")
      (node (ref "J1") (pin "NC1") (pinfunction "PAD1_NC1") (pintype "bidirectional"))
    )
    (net (code "45") (name "unconnected-(J1-PAD2-PadNC2)") (class "Default")
      (node (ref "J1") (pin "NC2") (pinfunction "PAD2_NC2") (pintype "bidirectional"))
    )
    (net (code "46") (name "unconnected-(J2-PAD1-PadNC1)") (class "Default")
      (node (ref "J2") (pin "NC1") (pinfunction "PAD1_NC1") (pintype "bidirectional"))
    )
    (net (code "47") (name "unconnected-(J2-PAD2-PadNC2)") (class "Default")
      (node (ref "J2") (pin "NC2") (pinfunction "PAD2_NC2") (pintype "bidirectional"))
    )
    (net (code "48") (name "unconnected-(J6-Pad6)") (class "Default")
      (node (ref "J6") (pin "6") (pinfunction "6_6") (pintype "passive"))
    )
    (net (code "49") (name "unconnected-(P1-PadD7)") (class "Default")
      (node (ref "P1") (pin "D7") (pinfunction "D7_D7") (pintype "bidirectional"))
    )
    (net (code "50") (name "unconnected-(P1-PadNC)") (class "Default")
      (node (ref "P1") (pin "NC") (pinfunction "NC_NC") (pintype "bidirectional"))
    )
    (net (code "51") (name "unconnected-(U1-NC-Pad3)") (class "Default")
      (node (ref "U1") (pin "3") (pinfunction "NC_3") (pintype "passive"))
    )
    (net (code "52") (name "unconnected-(U1-VOUT-Pad1)") (class "Default")
      (node (ref "U1") (pin "1") (pinfunction "VOUT_1") (pintype "passive"))
    )
    (net (code "53") (name "~{RST}") (class "Default")
      (node (ref "ATTINY85") (pin "6") (pinfunction "PB1(MISO)_6") (pintype "bidirectional"))
      (node (ref "ICSP") (pin "1") (pinfunction "MISO_1") (pintype "bidirectional"))
      (node (ref "P1") (pin "RST") (pinfunction "~{RST}_RST") (pintype "bidirectional"))
    )
    (net (code "54") (name "~{TINY-RST}") (class "Default")
      (node (ref "ATTINY85") (pin "1") (pinfunction "PB5(NRES)_1") (pintype "bidirectional"))
      (node (ref "ICSP") (pin "5") (pinfunction "~{RESET}_5") (pintype "input"))
      (node (ref "R3") (pin "1") (pinfunction "1_1") (pintype "passive"))
    )
  )
)
